# CANdiy-Shield_v20.net
KiCad netlist of a schematic drawn in EAGLE
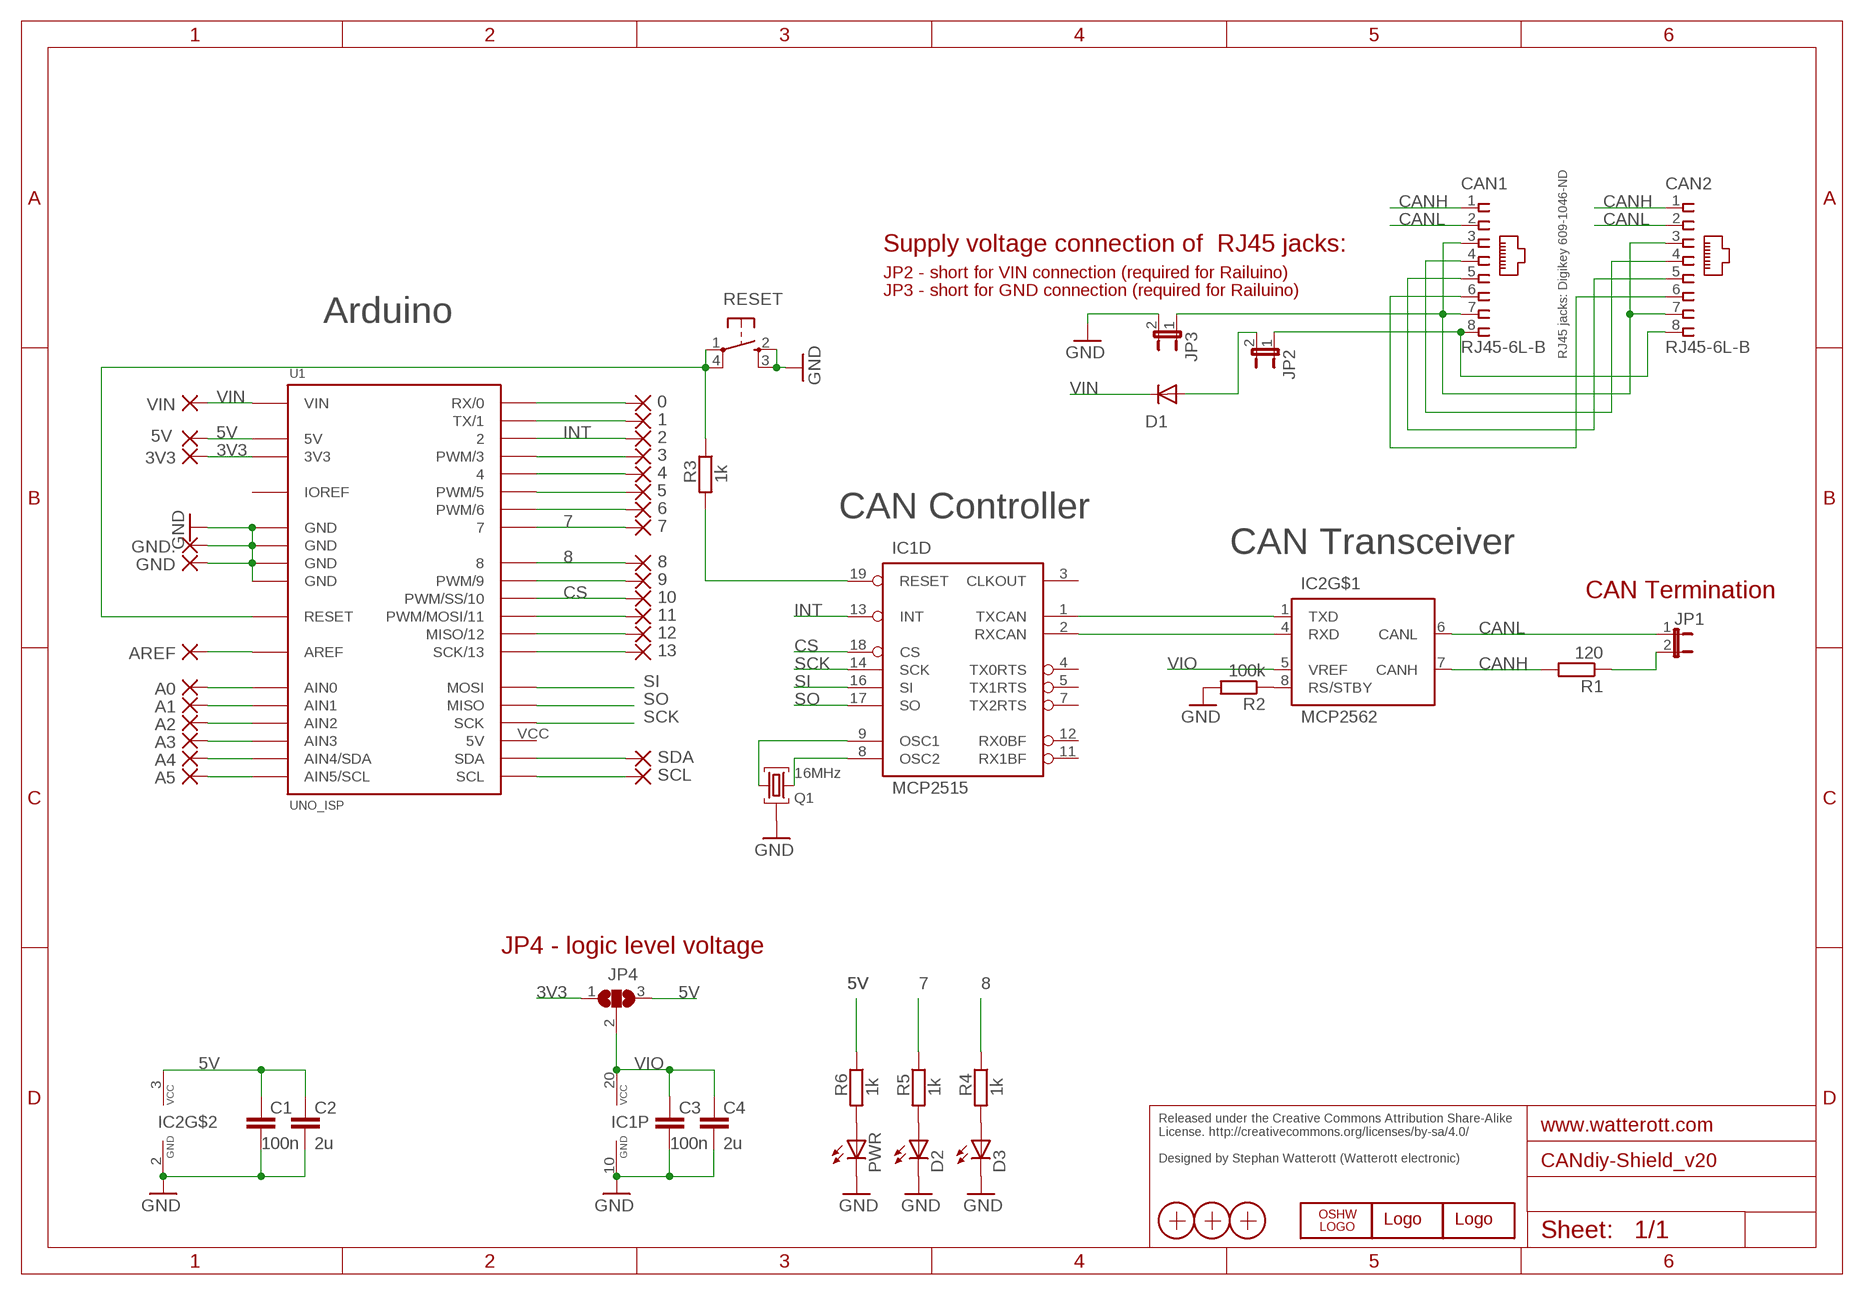
[diagram p0: schematic, sheet 1]

(export (version "E")
  (design (tool "Eeschema 10.0.6"))
  (components
    (comp (ref "0")
      (value "1,6/0,8")
      (footprint "eagle-import:1,6_0,8")
      (libsource (lib "eagle-import") (part "1,6/0,8"))
    )
    (comp (ref "1")
      (value "1,6/0,8")
      (footprint "eagle-import:1,6_0,8")
      (libsource (lib "eagle-import") (part "1,6/0,8"))
    )
    (comp (ref "2")
      (value "1,6/0,8")
      (footprint "eagle-import:1,6_0,8")
      (libsource (lib "eagle-import") (part "1,6/0,8"))
    )
    (comp (ref "3")
      (value "1,6/0,8")
      (footprint "eagle-import:1,6_0,8")
      (libsource (lib "eagle-import") (part "1,6/0,8"))
    )
    (comp (ref "3V3")
      (value "1,6/0,8")
      (footprint "eagle-import:1,6_0,8")
      (libsource (lib "eagle-import") (part "1,6/0,8"))
    )
    (comp (ref "4")
      (value "1,6/0,8")
      (footprint "eagle-import:1,6_0,8")
      (libsource (lib "eagle-import") (part "1,6/0,8"))
    )
    (comp (ref "5")
      (value "1,6/0,8")
      (footprint "eagle-import:1,6_0,8")
      (libsource (lib "eagle-import") (part "1,6/0,8"))
    )
    (comp (ref "5V")
      (value "1,6/0,8")
      (footprint "eagle-import:1,6_0,8")
      (libsource (lib "eagle-import") (part "1,6/0,8"))
    )
    (comp (ref "6")
      (value "1,6/0,8")
      (footprint "eagle-import:1,6_0,8")
      (libsource (lib "eagle-import") (part "1,6/0,8"))
    )
    (comp (ref "7")
      (value "1,6/0,8")
      (footprint "eagle-import:1,6_0,8")
      (libsource (lib "eagle-import") (part "1,6/0,8"))
    )
    (comp (ref "8")
      (value "1,6/0,8")
      (footprint "eagle-import:1,6_0,8")
      (libsource (lib "eagle-import") (part "1,6/0,8"))
    )
    (comp (ref "9")
      (value "1,6/0,8")
      (footprint "eagle-import:1,6_0,8")
      (libsource (lib "eagle-import") (part "1,6/0,8"))
    )
    (comp (ref "10")
      (value "1,6/0,8")
      (footprint "eagle-import:1,6_0,8")
      (libsource (lib "eagle-import") (part "1,6/0,8"))
    )
    (comp (ref "11")
      (value "1,6/0,8")
      (footprint "eagle-import:1,6_0,8")
      (libsource (lib "eagle-import") (part "1,6/0,8"))
    )
    (comp (ref "12")
      (value "1,6/0,8")
      (footprint "eagle-import:1,6_0,8")
      (libsource (lib "eagle-import") (part "1,6/0,8"))
    )
    (comp (ref "13")
      (value "1,6/0,8")
      (footprint "eagle-import:1,6_0,8")
      (libsource (lib "eagle-import") (part "1,6/0,8"))
    )
    (comp (ref "A0")
      (value "1,6/0,8")
      (footprint "eagle-import:1,6_0,8")
      (libsource (lib "eagle-import") (part "1,6/0,8"))
    )
    (comp (ref "A1")
      (value "1,6/0,8")
      (footprint "eagle-import:1,6_0,8")
      (libsource (lib "eagle-import") (part "1,6/0,8"))
    )
    (comp (ref "A2")
      (value "1,6/0,8")
      (footprint "eagle-import:1,6_0,8")
      (libsource (lib "eagle-import") (part "1,6/0,8"))
    )
    (comp (ref "A3")
      (value "1,6/0,8")
      (footprint "eagle-import:1,6_0,8")
      (libsource (lib "eagle-import") (part "1,6/0,8"))
    )
    (comp (ref "A4")
      (value "1,6/0,8")
      (footprint "eagle-import:1,6_0,8")
      (libsource (lib "eagle-import") (part "1,6/0,8"))
    )
    (comp (ref "A5")
      (value "1,6/0,8")
      (footprint "eagle-import:1,6_0,8")
      (libsource (lib "eagle-import") (part "1,6/0,8"))
    )
    (comp (ref "AREF")
      (value "1,6/0,8")
      (footprint "eagle-import:1,6_0,8")
      (libsource (lib "eagle-import") (part "1,6/0,8"))
    )
    (comp (ref "C1")
      (value "100n")
      (footprint "eagle-import:C0603")
      (libsource (lib "eagle-import") (part "C-EUC0603"))
    )
    (comp (ref "C2")
      (value "2u")
      (footprint "eagle-import:C0603")
      (libsource (lib "eagle-import") (part "C-EUC0603"))
    )
    (comp (ref "C3")
      (value "100n")
      (footprint "eagle-import:C0603")
      (libsource (lib "eagle-import") (part "C-EUC0603"))
    )
    (comp (ref "C4")
      (value "2u")
      (footprint "eagle-import:C0603")
      (libsource (lib "eagle-import") (part "C-EUC0603"))
    )
    (comp (ref "CAN1")
      (value "RJ45-6L-B")
      (footprint "eagle-import:RJ45-NO-SHIELD")
      (libsource (lib "eagle-import") (part "RJ45-6L-B"))
    )
    (comp (ref "CAN2")
      (value "RJ45-6L-B")
      (footprint "eagle-import:RJ45-NO-SHIELD")
      (libsource (lib "eagle-import") (part "RJ45-6L-B"))
    )
    (comp (ref "D1")
      (value "CGRM4001-G")
      (footprint "eagle-import:SOD-123_MINI-SMA")
      (libsource (lib "eagle-import") (part "CGRM400-G1"))
    )
    (comp (ref "D2")
      (value "LEDCHIPLED_0603")
      (footprint "eagle-import:CHIPLED_0603")
      (libsource (lib "eagle-import") (part "LEDCHIPLED_0603"))
    )
    (comp (ref "D3")
      (value "LEDCHIPLED_0603")
      (footprint "eagle-import:CHIPLED_0603")
      (libsource (lib "eagle-import") (part "LEDCHIPLED_0603"))
    )
    (comp (ref "GND")
      (value "1,6/0,8")
      (footprint "eagle-import:1,6_0,8")
      (libsource (lib "eagle-import") (part "1,6/0,8"))
    )
    (comp (ref "GND.")
      (value "1,6/0,8")
      (footprint "eagle-import:1,6_0,8")
      (libsource (lib "eagle-import") (part "1,6/0,8"))
    )
    (comp (ref "IC1")
      (value "MCP2515")
      (footprint "eagle-import:TSSOP20")
      (libsource (lib "eagle-import") (part "MCP2515ST"))
    )
    (comp (ref "IC2")
      (value "MCP2562")
      (footprint "eagle-import:SO08")
      (libsource (lib "eagle-import") (part "MCP2551SO8"))
    )
    (comp (ref "JP1")
      (value "JP1E")
      (footprint "eagle-import:JP1")
      (libsource (lib "eagle-import") (part "JP1E"))
    )
    (comp (ref "JP2")
      (value "JP1E")
      (footprint "eagle-import:JP1")
      (libsource (lib "eagle-import") (part "JP1E"))
    )
    (comp (ref "JP3")
      (value "JP1E")
      (footprint "eagle-import:JP1")
      (libsource (lib "eagle-import") (part "JP1E"))
    )
    (comp (ref "JP4")
      (value "SJ2W")
      (footprint "eagle-import:SJ_2")
      (libsource (lib "eagle-import") (part "SJ2W"))
    )
    (comp (ref "LOGO1")
      (value "LOGO-SPARK_PLACE")
      (footprint "eagle-import:SPARK_TPLACE")
      (libsource (lib "eagle-import") (part "LOGO-SPARK_PLACE"))
    )
    (comp (ref "LOGO2")
      (value "OSHW_LOGO_6MILX0100-NT")
      (footprint "eagle-import:OSHW_6X100_NOTEXT")
      (libsource (lib "eagle-import") (part "OSHW_LOGO_6MILX0100-NT"))
    )
    (comp (ref "PWR")
      (value "LEDCHIPLED_0603")
      (footprint "eagle-import:CHIPLED_0603")
      (libsource (lib "eagle-import") (part "LEDCHIPLED_0603"))
    )
    (comp (ref "Q1")
      (value "16MHz")
      (footprint "eagle-import:SMD_OSC_35X15")
      (libsource (lib "eagle-import") (part "SMD_OSC2"))
    )
    (comp (ref "R1")
      (value "120")
      (footprint "eagle-import:R0603")
      (libsource (lib "eagle-import") (part "resistor_R-EU_R0603"))
    )
    (comp (ref "R2")
      (value "100k")
      (footprint "eagle-import:R0603")
      (libsource (lib "eagle-import") (part "resistor_R-EU_R0603"))
    )
    (comp (ref "R3")
      (value "1k")
      (footprint "eagle-import:R0603")
      (libsource (lib "eagle-import") (part "R-EU_R0603"))
    )
    (comp (ref "R4")
      (value "1k")
      (footprint "eagle-import:R0603")
      (libsource (lib "eagle-import") (part "R-EU_R0603"))
    )
    (comp (ref "R5")
      (value "1k")
      (footprint "eagle-import:R0603")
      (libsource (lib "eagle-import") (part "R-EU_R0603"))
    )
    (comp (ref "R6")
      (value "1k")
      (footprint "eagle-import:R0603")
      (libsource (lib "eagle-import") (part "R-EU_R0603"))
    )
    (comp (ref "RESET")
      (value "SW_SMDS")
      (footprint "eagle-import:SW_SMD4")
      (libsource (lib "eagle-import") (part "SW_SMDS"))
    )
    (comp (ref "SCL")
      (value "1,6/0,8")
      (footprint "eagle-import:1,6_0,8")
      (libsource (lib "eagle-import") (part "1,6/0,8"))
    )
    (comp (ref "SDA")
      (value "1,6/0,8")
      (footprint "eagle-import:1,6_0,8")
      (libsource (lib "eagle-import") (part "1,6/0,8"))
    )
    (comp (ref "U$1")
      (value "WE-LOGO")
      (footprint "eagle-import:WE-LOGO")
      (libsource (lib "eagle-import") (part "WE-LOGO"))
    )
    (comp (ref "U1")
      (value "UNO_ISP")
      (footprint "eagle-import:UNO_ISP")
      (libsource (lib "eagle-import") (part "UNO_ISP"))
    )
    (comp (ref "VIN")
      (value "1,6/0,8")
      (footprint "eagle-import:1,6_0,8")
      (libsource (lib "eagle-import") (part "1,6/0,8"))
    )
    (comp (ref "X1")
      (value "PASSER")
      (footprint "eagle-import:PASSER")
      (libsource (lib "eagle-import") (part "PASSER"))
    )
    (comp (ref "X2")
      (value "PASSER")
      (footprint "eagle-import:PASSER")
      (libsource (lib "eagle-import") (part "PASSER"))
    )
    (comp (ref "X3")
      (value "PASSER")
      (footprint "eagle-import:PASSER")
      (libsource (lib "eagle-import") (part "PASSER"))
    )
  )
  (nets
    (net (code "1") (name "/3V3") (class "Default")
      (node (ref "3V3") (pin "1") (pinfunction "P_1") (pintype "passive"))
      (node (ref "JP4") (pin "1") (pinfunction "1_1") (pintype "passive"))
      (node (ref "U1") (pin "3V3") (pinfunction "3V3_3V3") (pintype "power_in"))
    )
    (net (code "2") (name "/5V") (class "Default")
      (node (ref "5V") (pin "1") (pinfunction "P_1") (pintype "passive"))
      (node (ref "C1") (pin "1") (pinfunction "1_1") (pintype "passive"))
      (node (ref "C2") (pin "1") (pinfunction "1_1") (pintype "passive"))
      (node (ref "IC2") (pin "3") (pinfunction "VCC_3") (pintype "power_in"))
      (node (ref "JP4") (pin "3") (pinfunction "3_3") (pintype "passive"))
      (node (ref "R6") (pin "1") (pinfunction "1_1") (pintype "passive"))
      (node (ref "U1") (pin "5V") (pinfunction "5V_5V") (pintype "power_in"))
    )
    (net (code "3") (name "/7") (class "Default")
      (node (ref "7") (pin "1") (pinfunction "P_1") (pintype "passive"))
      (node (ref "R5") (pin "1") (pinfunction "1_1") (pintype "passive"))
      (node (ref "U1") (pin "7") (pinfunction "7_7") (pintype "bidirectional"))
    )
    (net (code "4") (name "/8") (class "Default")
      (node (ref "8") (pin "1") (pinfunction "P_1") (pintype "passive"))
      (node (ref "R4") (pin "1") (pinfunction "1_1") (pintype "passive"))
      (node (ref "U1") (pin "8") (pinfunction "8_8") (pintype "bidirectional"))
    )
    (net (code "5") (name "/CANH") (class "Default")
      (node (ref "CAN1") (pin "1") (pinfunction "1_1") (pintype "passive"))
      (node (ref "CAN2") (pin "1") (pinfunction "1_1") (pintype "passive"))
      (node (ref "IC2") (pin "7") (pinfunction "CANH_7") (pintype "bidirectional"))
      (node (ref "R1") (pin "2") (pinfunction "2_2") (pintype "passive"))
    )
    (net (code "6") (name "/CANL") (class "Default")
      (node (ref "CAN1") (pin "2") (pinfunction "2_2") (pintype "passive"))
      (node (ref "CAN2") (pin "2") (pinfunction "2_2") (pintype "passive"))
      (node (ref "IC2") (pin "6") (pinfunction "CANL_6") (pintype "bidirectional"))
      (node (ref "JP1") (pin "1") (pinfunction "1_1") (pintype "passive"))
    )
    (net (code "7") (name "/CS") (class "Default")
      (node (ref "10") (pin "1") (pinfunction "P_1") (pintype "passive"))
      (node (ref "IC1") (pin "18") (pinfunction "CS_18") (pintype "input"))
      (node (ref "U1") (pin "10") (pinfunction "PWM/SS/10_10") (pintype "bidirectional"))
    )
    (net (code "8") (name "/INT") (class "Default")
      (node (ref "2") (pin "1") (pinfunction "P_1") (pintype "passive"))
      (node (ref "IC1") (pin "13") (pinfunction "INT_13") (pintype "output"))
      (node (ref "U1") (pin "2") (pinfunction "2_2") (pintype "bidirectional"))
    )
    (net (code "9") (name "/IOREF") (class "Default")
      (node (ref "U1") (pin "IOREF") (pinfunction "IOREF_IOREF") (pintype "power_in"))
    )
    (net (code "10") (name "/SCK") (class "Default")
      (node (ref "IC1") (pin "14") (pinfunction "SCK_14") (pintype "input"))
      (node (ref "U1") (pin "SCK") (pinfunction "SCK_SCK") (pintype "bidirectional"))
    )
    (net (code "11") (name "/SI") (class "Default")
      (node (ref "IC1") (pin "16") (pinfunction "SI_16") (pintype "input"))
      (node (ref "U1") (pin "MOSI") (pinfunction "MOSI_MOSI") (pintype "bidirectional"))
    )
    (net (code "12") (name "/SO") (class "Default")
      (node (ref "IC1") (pin "17") (pinfunction "SO_17") (pintype "output"))
      (node (ref "U1") (pin "MISO") (pinfunction "MISO_MISO") (pintype "bidirectional"))
    )
    (net (code "13") (name "/VIN") (class "Default")
      (node (ref "D1") (pin "C") (pinfunction "C_C") (pintype "passive"))
      (node (ref "U1") (pin "VIN") (pinfunction "VIN_VIN") (pintype "power_in"))
      (node (ref "VIN") (pin "1") (pinfunction "P_1") (pintype "passive"))
    )
    (net (code "14") (name "/VIO") (class "Default")
      (node (ref "C3") (pin "1") (pinfunction "1_1") (pintype "passive"))
      (node (ref "C4") (pin "1") (pinfunction "1_1") (pintype "passive"))
      (node (ref "IC1") (pin "20") (pinfunction "VCC_20") (pintype "power_in"))
      (node (ref "IC2") (pin "5") (pinfunction "VREF_5") (pintype "bidirectional"))
      (node (ref "JP4") (pin "2") (pinfunction "2_2") (pintype "passive"))
    )
    (net (code "15") (name "GND") (class "Default")
      (node (ref "C1") (pin "2") (pinfunction "2_2") (pintype "passive"))
      (node (ref "C2") (pin "2") (pinfunction "2_2") (pintype "passive"))
      (node (ref "C3") (pin "2") (pinfunction "2_2") (pintype "passive"))
      (node (ref "C4") (pin "2") (pinfunction "2_2") (pintype "passive"))
      (node (ref "D2") (pin "C") (pinfunction "C_C") (pintype "passive"))
      (node (ref "D3") (pin "C") (pinfunction "C_C") (pintype "passive"))
      (node (ref "GND") (pin "1") (pinfunction "P_1") (pintype "passive"))
      (node (ref "GND.") (pin "1") (pinfunction "P_1") (pintype "passive"))
      (node (ref "IC1") (pin "10") (pinfunction "GND_10") (pintype "power_in"))
      (node (ref "IC2") (pin "2") (pinfunction "GND_2") (pintype "power_in"))
      (node (ref "JP3") (pin "2") (pinfunction "2_2") (pintype "passive"))
      (node (ref "PWR") (pin "C") (pinfunction "C_C") (pintype "passive"))
      (node (ref "Q1") (pin "GND") (pinfunction "GND_GND") (pintype "passive"))
      (node (ref "R2") (pin "2") (pinfunction "2_2") (pintype "passive"))
      (node (ref "RESET") (pin "2") (pinfunction "S_2") (pintype "passive"))
      (node (ref "RESET") (pin "3") (pinfunction "S1_3") (pintype "passive"))
      (node (ref "U1") (pin "GND@1") (pinfunction "GND_GND@1") (pintype "power_in"))
      (node (ref "U1") (pin "GND@2") (pinfunction "GND_GND@2") (pintype "power_in"))
      (node (ref "U1") (pin "GND@3") (pinfunction "GND_GND@3") (pintype "power_in"))
      (node (ref "U1") (pin "GND@4") (pinfunction "GND_GND@4") (pintype "power_in"))
    )
    (net (code "16") (name "Net-(0-P)") (class "Default")
      (node (ref "0") (pin "1") (pinfunction "P_1") (pintype "passive"))
      (node (ref "U1") (pin "0") (pinfunction "RX/0_0") (pintype "bidirectional"))
    )
    (net (code "17") (name "Net-(1-P)") (class "Default")
      (node (ref "1") (pin "1") (pinfunction "P_1") (pintype "passive"))
      (node (ref "U1") (pin "1") (pinfunction "TX/1_1") (pintype "bidirectional"))
    )
    (net (code "18") (name "Net-(3-P)") (class "Default")
      (node (ref "3") (pin "1") (pinfunction "P_1") (pintype "passive"))
      (node (ref "U1") (pin "3") (pinfunction "PWM/3_3") (pintype "bidirectional"))
    )
    (net (code "19") (name "Net-(4-P)") (class "Default")
      (node (ref "4") (pin "1") (pinfunction "P_1") (pintype "passive"))
      (node (ref "U1") (pin "4") (pinfunction "4_4") (pintype "bidirectional"))
    )
    (net (code "20") (name "Net-(5-P)") (class "Default")
      (node (ref "5") (pin "1") (pinfunction "P_1") (pintype "passive"))
      (node (ref "U1") (pin "5") (pinfunction "PWM/5_5") (pintype "bidirectional"))
    )
    (net (code "21") (name "Net-(6-P)") (class "Default")
      (node (ref "6") (pin "1") (pinfunction "P_1") (pintype "passive"))
      (node (ref "U1") (pin "6") (pinfunction "PWM/6_6") (pintype "bidirectional"))
    )
    (net (code "22") (name "Net-(9-P)") (class "Default")
      (node (ref "9") (pin "1") (pinfunction "P_1") (pintype "passive"))
      (node (ref "U1") (pin "9") (pinfunction "PWM/9_9") (pintype "bidirectional"))
    )
    (net (code "23") (name "Net-(11-P)") (class "Default")
      (node (ref "11") (pin "1") (pinfunction "P_1") (pintype "passive"))
      (node (ref "U1") (pin "11") (pinfunction "PWM/MOSI/11_11") (pintype "bidirectional"))
    )
    (net (code "24") (name "Net-(12-P)") (class "Default")
      (node (ref "12") (pin "1") (pinfunction "P_1") (pintype "passive"))
      (node (ref "U1") (pin "12") (pinfunction "MISO/12_12") (pintype "bidirectional"))
    )
    (net (code "25") (name "Net-(13-P)") (class "Default")
      (node (ref "13") (pin "1") (pinfunction "P_1") (pintype "passive"))
      (node (ref "U1") (pin "13") (pinfunction "SCK/13_13") (pintype "bidirectional"))
    )
    (net (code "26") (name "Net-(A0-P)") (class "Default")
      (node (ref "A0") (pin "1") (pinfunction "P_1") (pintype "passive"))
      (node (ref "U1") (pin "AIN0") (pinfunction "AIN0_AIN0") (pintype "bidirectional"))
    )
    (net (code "27") (name "Net-(A1-P)") (class "Default")
      (node (ref "A1") (pin "1") (pinfunction "P_1") (pintype "passive"))
      (node (ref "U1") (pin "AIN1") (pinfunction "AIN1_AIN1") (pintype "bidirectional"))
    )
    (net (code "28") (name "Net-(A2-P)") (class "Default")
      (node (ref "A2") (pin "1") (pinfunction "P_1") (pintype "passive"))
      (node (ref "U1") (pin "AIN2") (pinfunction "AIN2_AIN2") (pintype "bidirectional"))
    )
    (net (code "29") (name "Net-(A3-P)") (class "Default")
      (node (ref "A3") (pin "1") (pinfunction "P_1") (pintype "passive"))
      (node (ref "U1") (pin "AIN3") (pinfunction "AIN3_AIN3") (pintype "bidirectional"))
    )
    (net (code "30") (name "Net-(A4-P)") (class "Default")
      (node (ref "A4") (pin "1") (pinfunction "P_1") (pintype "passive"))
      (node (ref "U1") (pin "AIN4") (pinfunction "AIN4/SDA_AIN4") (pintype "bidirectional"))
    )
    (net (code "31") (name "Net-(A5-P)") (class "Default")
      (node (ref "A5") (pin "1") (pinfunction "P_1") (pintype "passive"))
      (node (ref "U1") (pin "AIN5") (pinfunction "AIN5/SCL_AIN5") (pintype "bidirectional"))
    )
    (net (code "32") (name "Net-(AREF-P)") (class "Default")
      (node (ref "AREF") (pin "1") (pinfunction "P_1") (pintype "passive"))
      (node (ref "U1") (pin "AREF") (pinfunction "AREF_AREF") (pintype "power_in"))
    )
    (net (code "33") (name "Net-(CAN1-Pad3)") (class "Default")
      (node (ref "CAN1") (pin "3") (pinfunction "3_3") (pintype "passive"))
      (node (ref "CAN1") (pin "7") (pinfunction "7_7") (pintype "passive"))
      (node (ref "CAN2") (pin "3") (pinfunction "3_3") (pintype "passive"))
      (node (ref "CAN2") (pin "7") (pinfunction "7_7") (pintype "passive"))
      (node (ref "JP3") (pin "1") (pinfunction "1_1") (pintype "passive"))
    )
    (net (code "34") (name "Net-(CAN1-Pad4)") (class "Default")
      (node (ref "CAN1") (pin "4") (pinfunction "4_4") (pintype "passive"))
      (node (ref "CAN2") (pin "4") (pinfunction "4_4") (pintype "passive"))
    )
    (net (code "35") (name "Net-(CAN1-Pad5)") (class "Default")
      (node (ref "CAN1") (pin "5") (pinfunction "5_5") (pintype "passive"))
      (node (ref "CAN2") (pin "5") (pinfunction "5_5") (pintype "passive"))
    )
    (net (code "36") (name "Net-(CAN1-Pad6)") (class "Default")
      (node (ref "CAN1") (pin "6") (pinfunction "6_6") (pintype "passive"))
      (node (ref "CAN2") (pin "6") (pinfunction "6_6") (pintype "passive"))
    )
    (net (code "37") (name "Net-(CAN1-Pad8)") (class "Default")
      (node (ref "CAN1") (pin "8") (pinfunction "8_8") (pintype "passive"))
      (node (ref "CAN2") (pin "8") (pinfunction "8_8") (pintype "passive"))
      (node (ref "JP2") (pin "1") (pinfunction "1_1") (pintype "passive"))
    )
    (net (code "38") (name "Net-(D1-PadA)") (class "Default")
      (node (ref "D1") (pin "A") (pinfunction "A_A") (pintype "passive"))
      (node (ref "JP2") (pin "2") (pinfunction "2_2") (pintype "passive"))
    )
    (net (code "39") (name "Net-(D2-PadA)") (class "Default")
      (node (ref "D2") (pin "A") (pinfunction "A_A") (pintype "passive"))
      (node (ref "R5") (pin "2") (pinfunction "2_2") (pintype "passive"))
    )
    (net (code "40") (name "Net-(D3-PadA)") (class "Default")
      (node (ref "D3") (pin "A") (pinfunction "A_A") (pintype "passive"))
      (node (ref "R4") (pin "2") (pinfunction "2_2") (pintype "passive"))
    )
    (net (code "41") (name "Net-(IC1A-OSC1)") (class "Default")
      (node (ref "IC1") (pin "9") (pinfunction "OSC1_9") (pintype "input"))
      (node (ref "Q1") (pin "1") (pinfunction "1_1") (pintype "passive"))
    )
    (net (code "42") (name "Net-(IC1A-OSC2)") (class "Default")
      (node (ref "IC1") (pin "8") (pinfunction "OSC2_8") (pintype "input"))
      (node (ref "Q1") (pin "2") (pinfunction "2_2") (pintype "passive"))
    )
    (net (code "43") (name "Net-(IC1A-RESET)") (class "Default")
      (node (ref "IC1") (pin "19") (pinfunction "RESET_19") (pintype "input"))
      (node (ref "R3") (pin "2") (pinfunction "2_2") (pintype "passive"))
    )
    (net (code "44") (name "Net-(IC1A-RXCAN)") (class "Default")
      (node (ref "IC1") (pin "2") (pinfunction "RXCAN_2") (pintype "input"))
      (node (ref "IC2") (pin "4") (pinfunction "RXD_4") (pintype "bidirectional"))
    )
    (net (code "45") (name "Net-(IC1A-TXCAN)") (class "Default")
      (node (ref "IC1") (pin "1") (pinfunction "TXCAN_1") (pintype "output"))
      (node (ref "IC2") (pin "1") (pinfunction "TXD_1") (pintype "bidirectional"))
    )
    (net (code "46") (name "Net-(IC2A-RS)") (class "Default")
      (node (ref "IC2") (pin "8") (pinfunction "RS_8") (pintype "bidirectional"))
      (node (ref "R2") (pin "1") (pinfunction "1_1") (pintype "passive"))
    )
    (net (code "47") (name "Net-(JP1-Pad2)") (class "Default")
      (node (ref "JP1") (pin "2") (pinfunction "2_2") (pintype "passive"))
      (node (ref "R1") (pin "1") (pinfunction "1_1") (pintype "passive"))
    )
    (net (code "48") (name "Net-(PWR-PadA)") (class "Default")
      (node (ref "PWR") (pin "A") (pinfunction "A_A") (pintype "passive"))
      (node (ref "R6") (pin "2") (pinfunction "2_2") (pintype "passive"))
    )
    (net (code "49") (name "Net-(RESET-P)") (class "Default")
      (node (ref "R3") (pin "1") (pinfunction "1_1") (pintype "passive"))
      (node (ref "RESET") (pin "1") (pinfunction "P_1") (pintype "passive"))
      (node (ref "RESET") (pin "4") (pinfunction "P1_4") (pintype "passive"))
      (node (ref "U1") (pin "RST") (pinfunction "RESET_RST") (pintype "bidirectional"))
    )
    (net (code "50") (name "Net-(SCL-P)") (class "Default")
      (node (ref "SCL") (pin "1") (pinfunction "P_1") (pintype "passive"))
      (node (ref "U1") (pin "SCL") (pinfunction "SCL_SCL") (pintype "bidirectional"))
    )
    (net (code "51") (name "Net-(SDA-P)") (class "Default")
      (node (ref "SDA") (pin "1") (pinfunction "P_1") (pintype "passive"))
      (node (ref "U1") (pin "SDA") (pinfunction "SDA_SDA") (pintype "bidirectional"))
    )
    (net (code "52") (name "unconnected-(IC1A-CLKOUT-Pad3)") (class "Default")
      (node (ref "IC1") (pin "3") (pinfunction "CLKOUT_3") (pintype "output"))
    )
    (net (code "53") (name "unconnected-(IC1A-RX0BF-Pad12)") (class "Default")
      (node (ref "IC1") (pin "12") (pinfunction "RX0BF_12") (pintype "output"))
    )
    (net (code "54") (name "unconnected-(IC1A-RX1BF-Pad11)") (class "Default")
      (node (ref "IC1") (pin "11") (pinfunction "RX1BF_11") (pintype "output"))
    )
    (net (code "55") (name "unconnected-(IC1A-TX0RTS-Pad4)") (class "Default")
      (node (ref "IC1") (pin "4") (pinfunction "TX0RTS_4") (pintype "input"))
    )
    (net (code "56") (name "unconnected-(IC1A-TX1RTS-Pad5)") (class "Default")
      (node (ref "IC1") (pin "5") (pinfunction "TX1RTS_5") (pintype "input"))
    )
    (net (code "57") (name "unconnected-(IC1A-TX2RTS-Pad7)") (class "Default")
      (node (ref "IC1") (pin "7") (pinfunction "TX2RTS_7") (pintype "input"))
    )
    (net (code "58") (name "unconnected-(U1-5V-PadVCC)") (class "Default")
      (node (ref "U1") (pin "VCC") (pinfunction "5V_VCC") (pintype "bidirectional"))
    )
  )
)
